# PitotPboard3.net
KiCad netlist of a schematic drawn in EAGLE
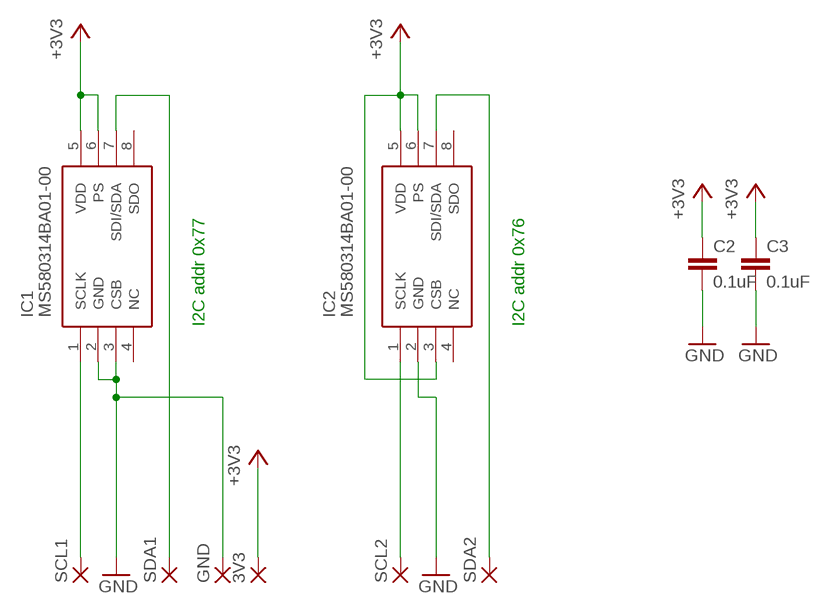
[diagram p0: schematic, sheet 1]

(export (version "E")
  (design (tool "Eeschema 10.0.6"))
  (components
    (comp (ref "3V3")
      (value "1,6/0,9")
      (footprint "eagle-import:1,6_0,9")
      (libsource (lib "eagle-import") (part "1,6/0,9"))
    )
    (comp (ref "C2")
      (value "0.1uF")
      (footprint "eagle-import:C0603K")
      (libsource (lib "eagle-import") (part "C-EUC0603K"))
    )
    (comp (ref "C3")
      (value "0.1uF")
      (footprint "eagle-import:C0603K")
      (libsource (lib "eagle-import") (part "C-EUC0603K"))
    )
    (comp (ref "GND")
      (value "1,6/0,9")
      (footprint "eagle-import:1,6_0,9")
      (libsource (lib "eagle-import") (part "1,6/0,9"))
    )
    (comp (ref "IC1")
      (value "MS580314BA01-00")
      (footprint "eagle-import:MS580314BA0100")
      (fields (field (name "MOUSER_PART_NUMBER") "824-MS580314BA01-00"))
      (libsource (lib "eagle-import") (part "MS580314BA01-00"))
    )
    (comp (ref "IC2")
      (value "MS580314BA01-00")
      (footprint "eagle-import:MS580314BA0100")
      (fields (field (name "MOUSER_PART_NUMBER") "824-MS580314BA01-00"))
      (libsource (lib "eagle-import") (part "MS580314BA01-00"))
    )
    (comp (ref "SCL1")
      (value "1,6/0,9")
      (footprint "eagle-import:1,6_0,9")
      (libsource (lib "eagle-import") (part "1,6/0,9"))
    )
    (comp (ref "SCL2")
      (value "1,6/0,9")
      (footprint "eagle-import:1,6_0,9")
      (libsource (lib "eagle-import") (part "1,6/0,9"))
    )
    (comp (ref "SDA1")
      (value "1,6/0,9")
      (footprint "eagle-import:1,6_0,9")
      (libsource (lib "eagle-import") (part "1,6/0,9"))
    )
    (comp (ref "SDA2")
      (value "1,6/0,9")
      (footprint "eagle-import:1,6_0,9")
      (libsource (lib "eagle-import") (part "1,6/0,9"))
    )
  )
  (nets
    (net (code "1") (name "+3V3") (class "Default")
      (node (ref "3V3") (pin "1") (pinfunction "P_1") (pintype "passive"))
      (node (ref "C2") (pin "1") (pinfunction "1_1") (pintype "passive"))
      (node (ref "C3") (pin "1") (pinfunction "1_1") (pintype "passive"))
      (node (ref "IC1") (pin "5") (pinfunction "VDD_5") (pintype "bidirectional"))
      (node (ref "IC1") (pin "6") (pinfunction "PS_6") (pintype "bidirectional"))
      (node (ref "IC2") (pin "3") (pinfunction "CSB_3") (pintype "bidirectional"))
      (node (ref "IC2") (pin "5") (pinfunction "VDD_5") (pintype "bidirectional"))
      (node (ref "IC2") (pin "6") (pinfunction "PS_6") (pintype "bidirectional"))
    )
    (net (code "2") (name "GND") (class "Default")
      (node (ref "C2") (pin "2") (pinfunction "2_2") (pintype "passive"))
      (node (ref "C3") (pin "2") (pinfunction "2_2") (pintype "passive"))
      (node (ref "GND") (pin "1") (pinfunction "P_1") (pintype "passive"))
      (node (ref "IC1") (pin "2") (pinfunction "GND_2") (pintype "bidirectional"))
      (node (ref "IC1") (pin "3") (pinfunction "CSB_3") (pintype "bidirectional"))
      (node (ref "IC2") (pin "2") (pinfunction "GND_2") (pintype "bidirectional"))
    )
    (net (code "3") (name "Net-(IC1-SCLK)") (class "Default")
      (node (ref "IC1") (pin "1") (pinfunction "SCLK_1") (pintype "bidirectional"))
      (node (ref "SCL1") (pin "1") (pinfunction "P_1") (pintype "passive"))
    )
    (net (code "4") (name "Net-(IC1-SDI{slash}SDA)") (class "Default")
      (node (ref "IC1") (pin "7") (pinfunction "SDI/SDA_7") (pintype "bidirectional"))
      (node (ref "SDA1") (pin "1") (pinfunction "P_1") (pintype "passive"))
    )
    (net (code "5") (name "Net-(IC2-SCLK)") (class "Default")
      (node (ref "IC2") (pin "1") (pinfunction "SCLK_1") (pintype "bidirectional"))
      (node (ref "SCL2") (pin "1") (pinfunction "P_1") (pintype "passive"))
    )
    (net (code "6") (name "Net-(IC2-SDI{slash}SDA)") (class "Default")
      (node (ref "IC2") (pin "7") (pinfunction "SDI/SDA_7") (pintype "bidirectional"))
      (node (ref "SDA2") (pin "1") (pinfunction "P_1") (pintype "passive"))
    )
    (net (code "7") (name "unconnected-(IC1-NC-Pad4)") (class "Default")
      (node (ref "IC1") (pin "4") (pinfunction "NC_4") (pintype "no_connect"))
    )
    (net (code "8") (name "unconnected-(IC1-SDO-Pad8)") (class "Default")
      (node (ref "IC1") (pin "8") (pinfunction "SDO_8") (pintype "bidirectional"))
    )
    (net (code "9") (name "unconnected-(IC2-NC-Pad4)") (class "Default")
      (node (ref "IC2") (pin "4") (pinfunction "NC_4") (pintype "no_connect"))
    )
    (net (code "10") (name "unconnected-(IC2-SDO-Pad8)") (class "Default")
      (node (ref "IC2") (pin "8") (pinfunction "SDO_8") (pintype "bidirectional"))
    )
  )
)
